# rev6_eagle7.net
KiCad netlist of a schematic drawn in EAGLE
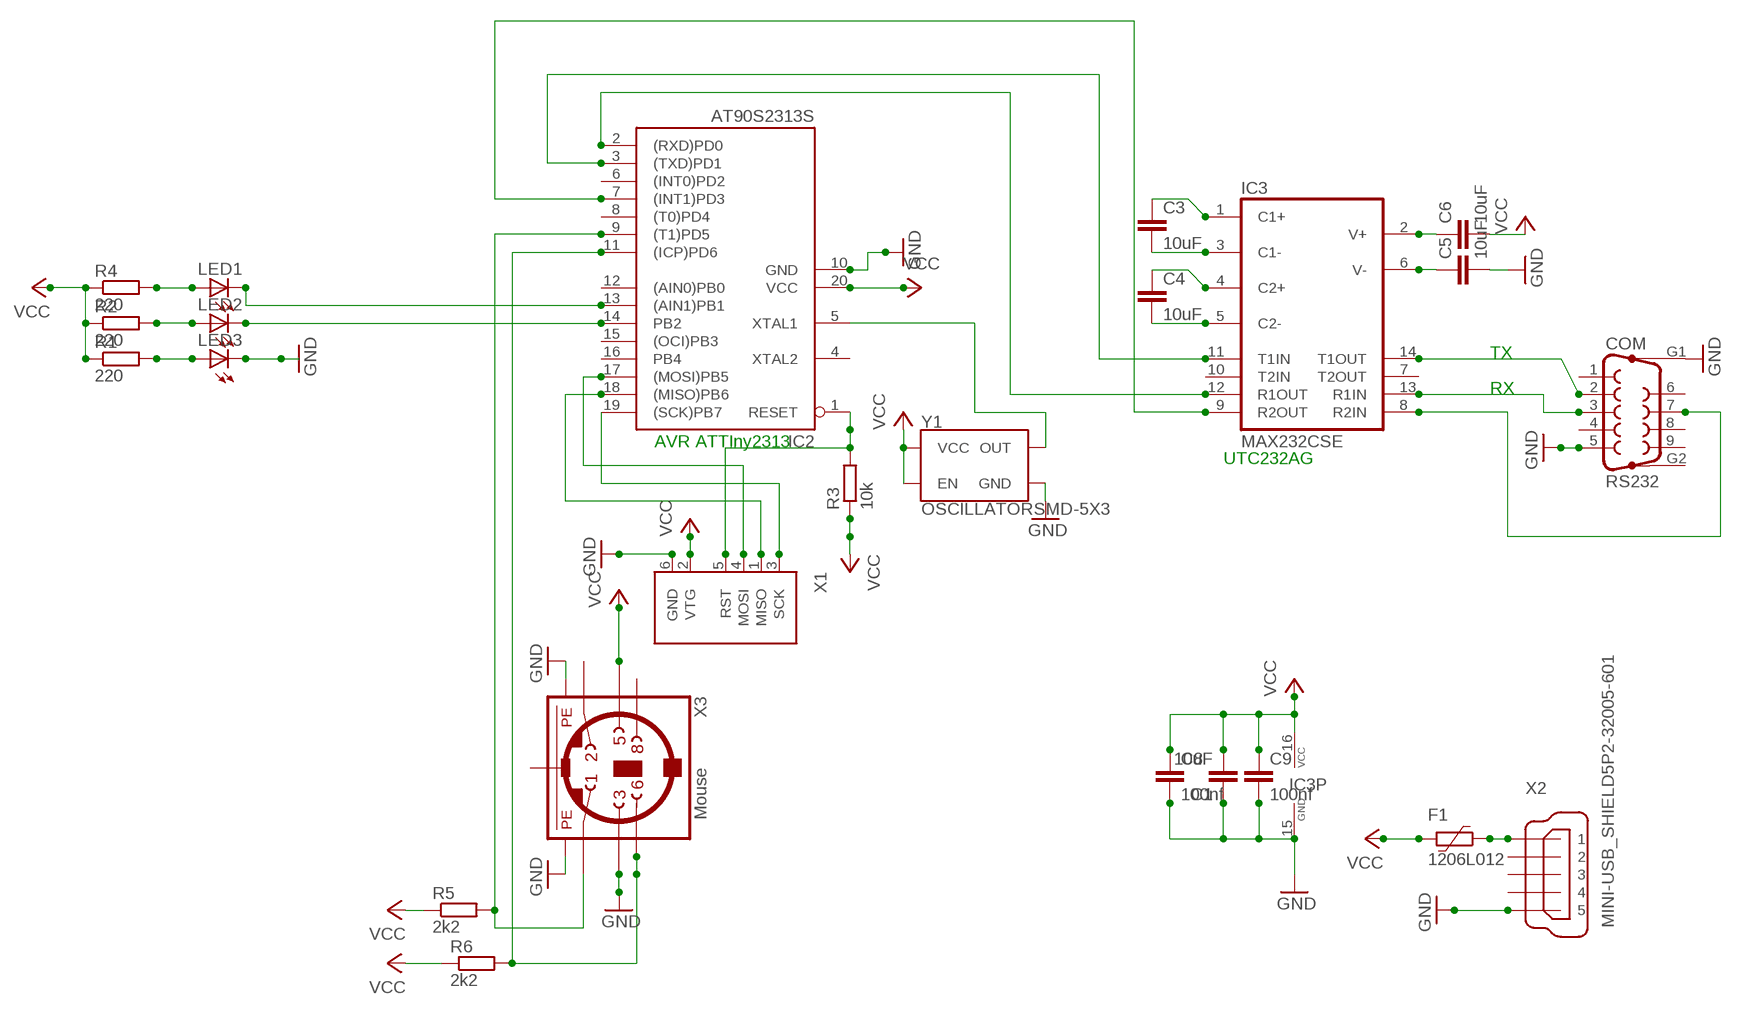
[diagram p0: schematic, sheet 1]

(export (version "E")
  (design (tool "Eeschema 10.0.6"))
  (components
    (comp (ref "C1")
      (value "10uF")
      (footprint "eagle-import:0805")
      (libsource (lib "eagle-import") (part "10UF-0805-25V-10%"))
    )
    (comp (ref "C3")
      (value "10uF")
      (footprint "eagle-import:0805")
      (libsource (lib "eagle-import") (part "10UF-0805-25V-10%"))
    )
    (comp (ref "C4")
      (value "10uF")
      (footprint "eagle-import:0805")
      (libsource (lib "eagle-import") (part "10UF-0805-25V-10%"))
    )
    (comp (ref "C5")
      (value "10uF")
      (footprint "eagle-import:0805")
      (libsource (lib "eagle-import") (part "10UF-0805-25V-10%"))
    )
    (comp (ref "C6")
      (value "10uF")
      (footprint "eagle-import:0805")
      (libsource (lib "eagle-import") (part "10UF-0805-25V-10%"))
    )
    (comp (ref "C8")
      (value "100nf")
      (footprint "eagle-import:C0805K")
      (libsource (lib "eagle-import") (part "C-EUC0805K"))
    )
    (comp (ref "C9")
      (value "100nf")
      (footprint "eagle-import:C0805K")
      (libsource (lib "eagle-import") (part "C-EUC0805K"))
    )
    (comp (ref "COM")
      (value "RS232")
      (footprint "eagle-import:F09HP")
      (libsource (lib "eagle-import") (part "F09HP"))
    )
    (comp (ref "F1")
      (value "1206L012")
      (footprint "eagle-import:1206L")
      (fields (field (name "MF") "Littelfuse"))
      (libsource (lib "eagle-import") (part "?1206L012"))
    )
    (comp (ref "IC2")
      (value "AT90S2313S")
      (footprint "eagle-import:SO20L")
      (libsource (lib "eagle-import") (part "AT90S2313S"))
    )
    (comp (ref "IC3")
      (value "MAX232CSE")
      (footprint "eagle-import:SO16")
      (libsource (lib "eagle-import") (part "MAX232SEC"))
    )
    (comp (ref "LED1")
      (value "LEDCHIPLED_0805")
      (footprint "eagle-import:CHIPLED_0805")
      (libsource (lib "eagle-import") (part "LEDCHIPLED_0805"))
    )
    (comp (ref "LED2")
      (value "LEDCHIPLED_0805")
      (footprint "eagle-import:CHIPLED_0805")
      (libsource (lib "eagle-import") (part "LEDCHIPLED_0805"))
    )
    (comp (ref "LED3")
      (value "LEDCHIPLED_0805")
      (footprint "eagle-import:CHIPLED_0805")
      (libsource (lib "eagle-import") (part "LEDCHIPLED_0805"))
    )
    (comp (ref "R1")
      (value "220")
      (footprint "eagle-import:R0805")
      (libsource (lib "eagle-import") (part "rcl@1_R-EU_R0805"))
    )
    (comp (ref "R2")
      (value "220")
      (footprint "eagle-import:R0805")
      (libsource (lib "eagle-import") (part "rcl@1_R-EU_R0805"))
    )
    (comp (ref "R3")
      (value "10k")
      (footprint "eagle-import:R1206")
      (libsource (lib "eagle-import") (part "R-EU_R1206"))
    )
    (comp (ref "R4")
      (value "220")
      (footprint "eagle-import:R0805")
      (libsource (lib "eagle-import") (part "rcl@1_R-EU_R0805"))
    )
    (comp (ref "R5")
      (value "2k2")
      (footprint "eagle-import:R1206")
      (libsource (lib "eagle-import") (part "R-EU_R1206"))
    )
    (comp (ref "R6")
      (value "2k2")
      (footprint "eagle-import:R1206")
      (libsource (lib "eagle-import") (part "R-EU_R1206"))
    )
    (comp (ref "X1")
      (value "AVRISP6PINHEADER")
      (footprint "eagle-import:6PINHEADER")
      (libsource (lib "eagle-import") (part "AVRISP6PINHEADER"))
    )
    (comp (ref "X2")
      (value "MINI-USB_SHIELD5P2-32005-601")
      (footprint "eagle-import:32005-601")
      (libsource (lib "eagle-import") (part "MINI-USB_SHIELD5P2-32005-601"))
    )
    (comp (ref "X3")
      (value "Mouse")
      (footprint "eagle-import:M_DIN6")
      (libsource (lib "eagle-import") (part "MINI_DIN_6"))
    )
    (comp (ref "Y1")
      (value "OSCILLATORSMD-5X3")
      (footprint "eagle-import:OSCILLATOR-SMD-5X3.2")
      (libsource (lib "eagle-import") (part "OSCILLATORSMD-5X3"))
    )
  )
  (nets
    (net (code "1") (name "/PE2") (class "Default")
      (node (ref "X3") (pin "SH2") (pinfunction "PE2_SH2") (pintype "power_in"))
    )
    (net (code "2") (name "GND") (class "Default")
      (node (ref "C1") (pin "1") (pinfunction "1_1") (pintype "passive"))
      (node (ref "C5") (pin "2") (pinfunction "2_2") (pintype "passive"))
      (node (ref "C8") (pin "2") (pinfunction "2_2") (pintype "passive"))
      (node (ref "C9") (pin "2") (pinfunction "2_2") (pintype "passive"))
      (node (ref "COM") (pin "5") (pinfunction "5_5") (pintype "passive"))
      (node (ref "COM") (pin "G1") (pinfunction "G1_G1") (pintype "passive"))
      (node (ref "IC2") (pin "10") (pinfunction "GND_10") (pintype "power_in"))
      (node (ref "IC3") (pin "15") (pinfunction "GND_15") (pintype "power_in"))
      (node (ref "LED3") (pin "C") (pinfunction "C_C") (pintype "passive"))
      (node (ref "X1") (pin "6") (pinfunction "GND_6") (pintype "bidirectional"))
      (node (ref "X2") (pin "5") (pinfunction "5_5") (pintype "passive"))
      (node (ref "X3") (pin "3") (pinfunction "3_3") (pintype "passive"))
      (node (ref "X3") (pin "SH1") (pinfunction "PE1_SH1") (pintype "power_in"))
      (node (ref "X3") (pin "SH3") (pinfunction "PE3_SH3") (pintype "power_in"))
      (node (ref "Y1") (pin "2") (pinfunction "GND_2") (pintype "bidirectional"))
    )
    (net (code "3") (name "Net-(F1-Pad1)") (class "Default")
      (node (ref "F1") (pin "1") (pinfunction "1_1") (pintype "passive"))
      (node (ref "X2") (pin "1") (pinfunction "1_1") (pintype "passive"))
    )
    (net (code "4") (name "Net-(IC2-(AIN1)PB1)") (class "Default")
      (node (ref "IC2") (pin "13") (pinfunction "(AIN1)PB1_13") (pintype "bidirectional"))
      (node (ref "LED1") (pin "C") (pinfunction "C_C") (pintype "passive"))
    )
    (net (code "5") (name "Net-(IC2-(ICP)PD6)") (class "Default")
      (node (ref "IC2") (pin "11") (pinfunction "(ICP)PD6_11") (pintype "bidirectional"))
      (node (ref "R6") (pin "2") (pinfunction "2_2") (pintype "passive"))
      (node (ref "X3") (pin "6") (pinfunction "6_6") (pintype "passive"))
    )
    (net (code "6") (name "Net-(IC2-(INT1)PD3)") (class "Default")
      (node (ref "IC2") (pin "7") (pinfunction "(INT1)PD3_7") (pintype "bidirectional"))
      (node (ref "IC3") (pin "9") (pinfunction "R2OUT_9") (pintype "output"))
    )
    (net (code "7") (name "Net-(IC2-(MISO)PB6)") (class "Default")
      (node (ref "IC2") (pin "18") (pinfunction "(MISO)PB6_18") (pintype "bidirectional"))
      (node (ref "X1") (pin "1") (pinfunction "MISO_1") (pintype "bidirectional"))
    )
    (net (code "8") (name "Net-(IC2-(MOSI)PB5)") (class "Default")
      (node (ref "IC2") (pin "17") (pinfunction "(MOSI)PB5_17") (pintype "bidirectional"))
      (node (ref "X1") (pin "4") (pinfunction "MOSI_4") (pintype "bidirectional"))
    )
    (net (code "9") (name "Net-(IC2-(RXD)PD0)") (class "Default")
      (node (ref "IC2") (pin "2") (pinfunction "(RXD)PD0_2") (pintype "bidirectional"))
      (node (ref "IC3") (pin "12") (pinfunction "R1OUT_12") (pintype "output"))
    )
    (net (code "10") (name "Net-(IC2-(SCK)PB7)") (class "Default")
      (node (ref "IC2") (pin "19") (pinfunction "(SCK)PB7_19") (pintype "bidirectional"))
      (node (ref "X1") (pin "3") (pinfunction "SCK_3") (pintype "bidirectional"))
    )
    (net (code "11") (name "Net-(IC2-(T1)PD5)") (class "Default")
      (node (ref "IC2") (pin "9") (pinfunction "(T1)PD5_9") (pintype "bidirectional"))
      (node (ref "R5") (pin "2") (pinfunction "2_2") (pintype "passive"))
      (node (ref "X3") (pin "1") (pinfunction "1_1") (pintype "passive"))
    )
    (net (code "12") (name "Net-(IC2-(TXD)PD1)") (class "Default")
      (node (ref "IC2") (pin "3") (pinfunction "(TXD)PD1_3") (pintype "bidirectional"))
      (node (ref "IC3") (pin "11") (pinfunction "T1IN_11") (pintype "input"))
    )
    (net (code "13") (name "Net-(IC2-PB2)") (class "Default")
      (node (ref "IC2") (pin "14") (pinfunction "PB2_14") (pintype "bidirectional"))
      (node (ref "LED2") (pin "C") (pinfunction "C_C") (pintype "passive"))
    )
    (net (code "14") (name "Net-(IC2-RESET)") (class "Default")
      (node (ref "IC2") (pin "1") (pinfunction "RESET_1") (pintype "bidirectional"))
      (node (ref "R3") (pin "2") (pinfunction "2_2") (pintype "passive"))
      (node (ref "X1") (pin "5") (pinfunction "RST_5") (pintype "bidirectional"))
    )
    (net (code "15") (name "Net-(IC2-XTAL1)") (class "Default")
      (node (ref "IC2") (pin "5") (pinfunction "XTAL1_5") (pintype "bidirectional"))
      (node (ref "Y1") (pin "3") (pinfunction "OUT_3") (pintype "bidirectional"))
    )
    (net (code "16") (name "Net-(IC3A-C1+)") (class "Default")
      (node (ref "C3") (pin "1") (pinfunction "1_1") (pintype "passive"))
      (node (ref "IC3") (pin "1") (pinfunction "C1+_1") (pintype "bidirectional"))
    )
    (net (code "17") (name "Net-(IC3A-C1-)") (class "Default")
      (node (ref "C3") (pin "2") (pinfunction "2_2") (pintype "passive"))
      (node (ref "IC3") (pin "3") (pinfunction "C1-_3") (pintype "bidirectional"))
    )
    (net (code "18") (name "Net-(IC3A-C2+)") (class "Default")
      (node (ref "C4") (pin "1") (pinfunction "1_1") (pintype "passive"))
      (node (ref "IC3") (pin "4") (pinfunction "C2+_4") (pintype "bidirectional"))
    )
    (net (code "19") (name "Net-(IC3A-C2-)") (class "Default")
      (node (ref "C4") (pin "2") (pinfunction "2_2") (pintype "passive"))
      (node (ref "IC3") (pin "5") (pinfunction "C2-_5") (pintype "bidirectional"))
    )
    (net (code "20") (name "Net-(IC3A-R1IN)") (class "Default")
      (node (ref "COM") (pin "3") (pinfunction "3_3") (pintype "passive"))
      (node (ref "IC3") (pin "13") (pinfunction "R1IN_13") (pintype "input"))
    )
    (net (code "21") (name "Net-(IC3A-R2IN)") (class "Default")
      (node (ref "COM") (pin "7") (pinfunction "7_7") (pintype "passive"))
      (node (ref "IC3") (pin "8") (pinfunction "R2IN_8") (pintype "input"))
    )
    (net (code "22") (name "Net-(IC3A-T1OUT)") (class "Default")
      (node (ref "COM") (pin "2") (pinfunction "2_2") (pintype "passive"))
      (node (ref "IC3") (pin "14") (pinfunction "T1OUT_14") (pintype "output"))
    )
    (net (code "23") (name "Net-(IC3A-V+)") (class "Default")
      (node (ref "C6") (pin "1") (pinfunction "1_1") (pintype "passive"))
      (node (ref "IC3") (pin "2") (pinfunction "V+_2") (pintype "bidirectional"))
    )
    (net (code "24") (name "Net-(IC3A-V-)") (class "Default")
      (node (ref "C5") (pin "1") (pinfunction "1_1") (pintype "passive"))
      (node (ref "IC3") (pin "6") (pinfunction "V-_6") (pintype "bidirectional"))
    )
    (net (code "25") (name "Net-(LED1-PadA)") (class "Default")
      (node (ref "LED1") (pin "A") (pinfunction "A_A") (pintype "passive"))
      (node (ref "R4") (pin "2") (pinfunction "2_2") (pintype "passive"))
    )
    (net (code "26") (name "Net-(LED2-PadA)") (class "Default")
      (node (ref "LED2") (pin "A") (pinfunction "A_A") (pintype "passive"))
      (node (ref "R2") (pin "2") (pinfunction "2_2") (pintype "passive"))
    )
    (net (code "27") (name "Net-(LED3-PadA)") (class "Default")
      (node (ref "LED3") (pin "A") (pinfunction "A_A") (pintype "passive"))
      (node (ref "R1") (pin "2") (pinfunction "2_2") (pintype "passive"))
    )
    (net (code "28") (name "VCC") (class "Default")
      (node (ref "C1") (pin "2") (pinfunction "2_2") (pintype "passive"))
      (node (ref "C6") (pin "2") (pinfunction "2_2") (pintype "passive"))
      (node (ref "C8") (pin "1") (pinfunction "1_1") (pintype "passive"))
      (node (ref "C9") (pin "1") (pinfunction "1_1") (pintype "passive"))
      (node (ref "F1") (pin "2") (pinfunction "2_2") (pintype "passive"))
      (node (ref "IC2") (pin "20") (pinfunction "VCC_20") (pintype "power_in"))
      (node (ref "IC3") (pin "16") (pinfunction "VCC_16") (pintype "power_in"))
      (node (ref "R1") (pin "1") (pinfunction "1_1") (pintype "passive"))
      (node (ref "R2") (pin "1") (pinfunction "1_1") (pintype "passive"))
      (node (ref "R3") (pin "1") (pinfunction "1_1") (pintype "passive"))
      (node (ref "R4") (pin "1") (pinfunction "1_1") (pintype "passive"))
      (node (ref "R5") (pin "1") (pinfunction "1_1") (pintype "passive"))
      (node (ref "R6") (pin "1") (pinfunction "1_1") (pintype "passive"))
      (node (ref "X1") (pin "2") (pinfunction "VTG_2") (pintype "bidirectional"))
      (node (ref "X3") (pin "5") (pinfunction "5_5") (pintype "passive"))
      (node (ref "Y1") (pin "1") (pinfunction "EN_1") (pintype "bidirectional"))
      (node (ref "Y1") (pin "4") (pinfunction "VCC_4") (pintype "bidirectional"))
    )
    (net (code "29") (name "unconnected-(COM-Pad1)") (class "Default")
      (node (ref "COM") (pin "1") (pinfunction "1_1") (pintype "passive"))
    )
    (net (code "30") (name "unconnected-(COM-Pad4)") (class "Default")
      (node (ref "COM") (pin "4") (pinfunction "4_4") (pintype "passive"))
    )
    (net (code "31") (name "unconnected-(COM-Pad6)") (class "Default")
      (node (ref "COM") (pin "6") (pinfunction "6_6") (pintype "passive"))
    )
    (net (code "32") (name "unconnected-(COM-Pad8)") (class "Default")
      (node (ref "COM") (pin "8") (pinfunction "8_8") (pintype "passive"))
    )
    (net (code "33") (name "unconnected-(COM-Pad9)") (class "Default")
      (node (ref "COM") (pin "9") (pinfunction "9_9") (pintype "passive"))
    )
    (net (code "34") (name "unconnected-(COM-PadG2)") (class "Default")
      (node (ref "COM") (pin "G2") (pinfunction "G2_G2") (pintype "passive"))
    )
    (net (code "35") (name "unconnected-(IC2-(AIN0)PB0-Pad12)") (class "Default")
      (node (ref "IC2") (pin "12") (pinfunction "(AIN0)PB0_12") (pintype "bidirectional"))
    )
    (net (code "36") (name "unconnected-(IC2-(INT0)PD2-Pad6)") (class "Default")
      (node (ref "IC2") (pin "6") (pinfunction "(INT0)PD2_6") (pintype "bidirectional"))
    )
    (net (code "37") (name "unconnected-(IC2-(OCI)PB3-Pad15)") (class "Default")
      (node (ref "IC2") (pin "15") (pinfunction "(OCI)PB3_15") (pintype "bidirectional"))
    )
    (net (code "38") (name "unconnected-(IC2-(T0)PD4-Pad8)") (class "Default")
      (node (ref "IC2") (pin "8") (pinfunction "(T0)PD4_8") (pintype "bidirectional"))
    )
    (net (code "39") (name "unconnected-(IC2-PB4-Pad16)") (class "Default")
      (node (ref "IC2") (pin "16") (pinfunction "PB4_16") (pintype "bidirectional"))
    )
    (net (code "40") (name "unconnected-(IC2-XTAL2-Pad4)") (class "Default")
      (node (ref "IC2") (pin "4") (pinfunction "XTAL2_4") (pintype "bidirectional"))
    )
    (net (code "41") (name "unconnected-(IC3A-T2IN-Pad10)") (class "Default")
      (node (ref "IC3") (pin "10") (pinfunction "T2IN_10") (pintype "input"))
    )
    (net (code "42") (name "unconnected-(IC3A-T2OUT-Pad7)") (class "Default")
      (node (ref "IC3") (pin "7") (pinfunction "T2OUT_7") (pintype "output"))
    )
    (net (code "43") (name "unconnected-(X2-Pad2)") (class "Default")
      (node (ref "X2") (pin "2") (pinfunction "2_2") (pintype "passive"))
    )
    (net (code "44") (name "unconnected-(X2-Pad3)") (class "Default")
      (node (ref "X2") (pin "3") (pinfunction "3_3") (pintype "passive"))
    )
    (net (code "45") (name "unconnected-(X2-Pad4)") (class "Default")
      (node (ref "X2") (pin "4") (pinfunction "4_4") (pintype "passive"))
    )
    (net (code "46") (name "unconnected-(X3-Pad2)") (class "Default")
      (node (ref "X3") (pin "2") (pinfunction "2_2") (pintype "passive"))
    )
    (net (code "47") (name "unconnected-(X3-Pad8)") (class "Default")
      (node (ref "X3") (pin "8") (pinfunction "8_8") (pintype "passive"))
    )
  )
)
